# Input.net
KiCad netlist of a schematic drawn in Altium Designer
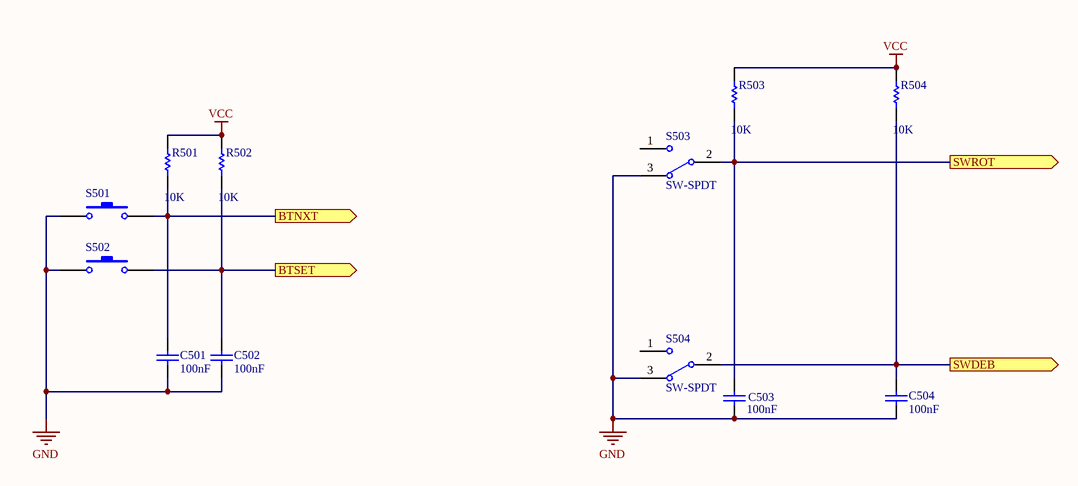
[diagram p0: Input.SchDoc]

(export (version "E")
  (design (tool "Eeschema 10.0.6"))
  (components
    (comp (ref "C501")
      (value "100nF")
      (footprint "RCL 0805")
      (description "Capacitor (Semiconductor SIM Model)")
      (fields (field (name "Comment") "Cap Semi") (field (name "PUBLISHER") "Altium Limited"))
      (libsource (lib "Miscellaneous Devices") (part "Cap Semi"))
    )
    (comp (ref "C502")
      (value "100nF")
      (footprint "RCL 0805")
      (description "Capacitor (Semiconductor SIM Model)")
      (fields (field (name "Comment") "Cap Semi") (field (name "PUBLISHER") "Altium Limited"))
      (libsource (lib "Miscellaneous Devices") (part "Cap Semi"))
    )
    (comp (ref "C503")
      (value "100nF")
      (footprint "RCL 0805")
      (description "Capacitor (Semiconductor SIM Model)")
      (fields (field (name "Comment") "Cap Semi") (field (name "PUBLISHER") "Altium Limited"))
      (libsource (lib "Miscellaneous Devices") (part "Cap Semi"))
    )
    (comp (ref "C504")
      (value "100nF")
      (footprint "RCL 0805")
      (description "Capacitor (Semiconductor SIM Model)")
      (fields (field (name "Comment") "Cap Semi") (field (name "PUBLISHER") "Altium Limited"))
      (libsource (lib "Miscellaneous Devices") (part "Cap Semi"))
    )
    (comp (ref "R501")
      (value "10K")
      (footprint "RCL 0805")
      (fields (field (name "Comment") "ERA6Y") (field (name "PUBLISHER") "Altium Limited"))
      (libsource (lib "Panasonic Resistor") (part "ERA6Y"))
    )
    (comp (ref "R502")
      (value "10K")
      (footprint "RCL 0805")
      (fields (field (name "Comment") "ERA6Y") (field (name "PUBLISHER") "Altium Limited"))
      (libsource (lib "Panasonic Resistor") (part "ERA6Y"))
    )
    (comp (ref "R503")
      (value "10K")
      (footprint "RCL 0805")
      (fields (field (name "Comment") "ERA6Y") (field (name "PUBLISHER") "Altium Limited"))
      (libsource (lib "Panasonic Resistor") (part "ERA6Y"))
    )
    (comp (ref "R504")
      (value "10K")
      (footprint "RCL 0805")
      (fields (field (name "Comment") "ERA6Y") (field (name "PUBLISHER") "Altium Limited"))
      (libsource (lib "Panasonic Resistor") (part "ERA6Y"))
    )
    (comp (ref "S501")
      (value "SW-PB")
      (footprint "Square SMD Switch 01")
      (description "Switch")
      (fields (field (name "PUBLISHER") "Altium Limited"))
      (libsource (lib "Miscellaneous Devices") (part "SW-PB"))
    )
    (comp (ref "S502")
      (value "SW-PB")
      (footprint "Square SMD Switch 01")
      (description "Switch")
      (fields (field (name "PUBLISHER") "Altium Limited"))
      (libsource (lib "Miscellaneous Devices") (part "SW-PB"))
    )
    (comp (ref "S503")
      (value "SW-SPDT")
      (footprint "TL36WW15050")
      (description "SPDT Subminiature Toggle Switch, Right Angle Mounting, Vertical Actuation")
      (fields (field (name "PUBLISHER") "Altium Limited"))
      (libsource (lib "Miscellaneous Devices") (part "SW-SPDT"))
    )
    (comp (ref "S504")
      (value "SW-SPDT")
      (footprint "TL36WW15050")
      (description "SPDT Subminiature Toggle Switch, Right Angle Mounting, Vertical Actuation")
      (fields (field (name "PUBLISHER") "Altium Limited"))
      (libsource (lib "Miscellaneous Devices") (part "SW-SPDT"))
    )
  )
  (nets
    (net (code "1") (name "/BTNXT") (class "Default")
      (node (ref "C501") (pin "2") (pinfunction "2_2") (pintype "passive"))
      (node (ref "R501") (pin "1") (pinfunction "1_1") (pintype "passive"))
      (node (ref "S501") (pin "2") (pinfunction "2_2") (pintype "passive"))
    )
    (net (code "2") (name "/BTSET") (class "Default")
      (node (ref "C502") (pin "2") (pinfunction "2_2") (pintype "passive"))
      (node (ref "R502") (pin "1") (pinfunction "1_1") (pintype "passive"))
      (node (ref "S502") (pin "2") (pinfunction "2_2") (pintype "passive"))
    )
    (net (code "3") (name "/SWDEB") (class "Default")
      (node (ref "C504") (pin "2") (pinfunction "2_2") (pintype "passive"))
      (node (ref "R504") (pin "1") (pinfunction "1_1") (pintype "passive"))
      (node (ref "S504") (pin "2") (pinfunction "2_2") (pintype "passive"))
    )
    (net (code "4") (name "/SWROT") (class "Default")
      (node (ref "C503") (pin "2") (pinfunction "2_2") (pintype "passive"))
      (node (ref "R503") (pin "1") (pinfunction "1_1") (pintype "passive"))
      (node (ref "S503") (pin "2") (pinfunction "2_2") (pintype "passive"))
    )
    (net (code "5") (name "GND") (class "Default")
      (node (ref "C501") (pin "1") (pinfunction "1_1") (pintype "passive"))
      (node (ref "C502") (pin "1") (pinfunction "1_1") (pintype "passive"))
      (node (ref "C503") (pin "1") (pinfunction "1_1") (pintype "passive"))
      (node (ref "C504") (pin "1") (pinfunction "1_1") (pintype "passive"))
      (node (ref "S501") (pin "1") (pinfunction "1_1") (pintype "passive"))
      (node (ref "S502") (pin "1") (pinfunction "1_1") (pintype "passive"))
      (node (ref "S503") (pin "3") (pinfunction "3_3") (pintype "passive"))
      (node (ref "S504") (pin "3") (pinfunction "3_3") (pintype "passive"))
    )
    (net (code "6") (name "VCC") (class "Default")
      (node (ref "R501") (pin "2") (pinfunction "2_2") (pintype "passive"))
      (node (ref "R502") (pin "2") (pinfunction "2_2") (pintype "passive"))
      (node (ref "R503") (pin "2") (pinfunction "2_2") (pintype "passive"))
      (node (ref "R504") (pin "2") (pinfunction "2_2") (pintype "passive"))
    )
    (net (code "7") (name "unconnected-(S503-Pad1)") (class "Default")
      (node (ref "S503") (pin "1") (pinfunction "1_1") (pintype "passive"))
    )
    (net (code "8") (name "unconnected-(S504-Pad1)") (class "Default")
      (node (ref "S504") (pin "1") (pinfunction "1_1") (pintype "passive"))
    )
  )
)
